# xmegs_breakout.net
KiCad netlist of a schematic drawn in EAGLE
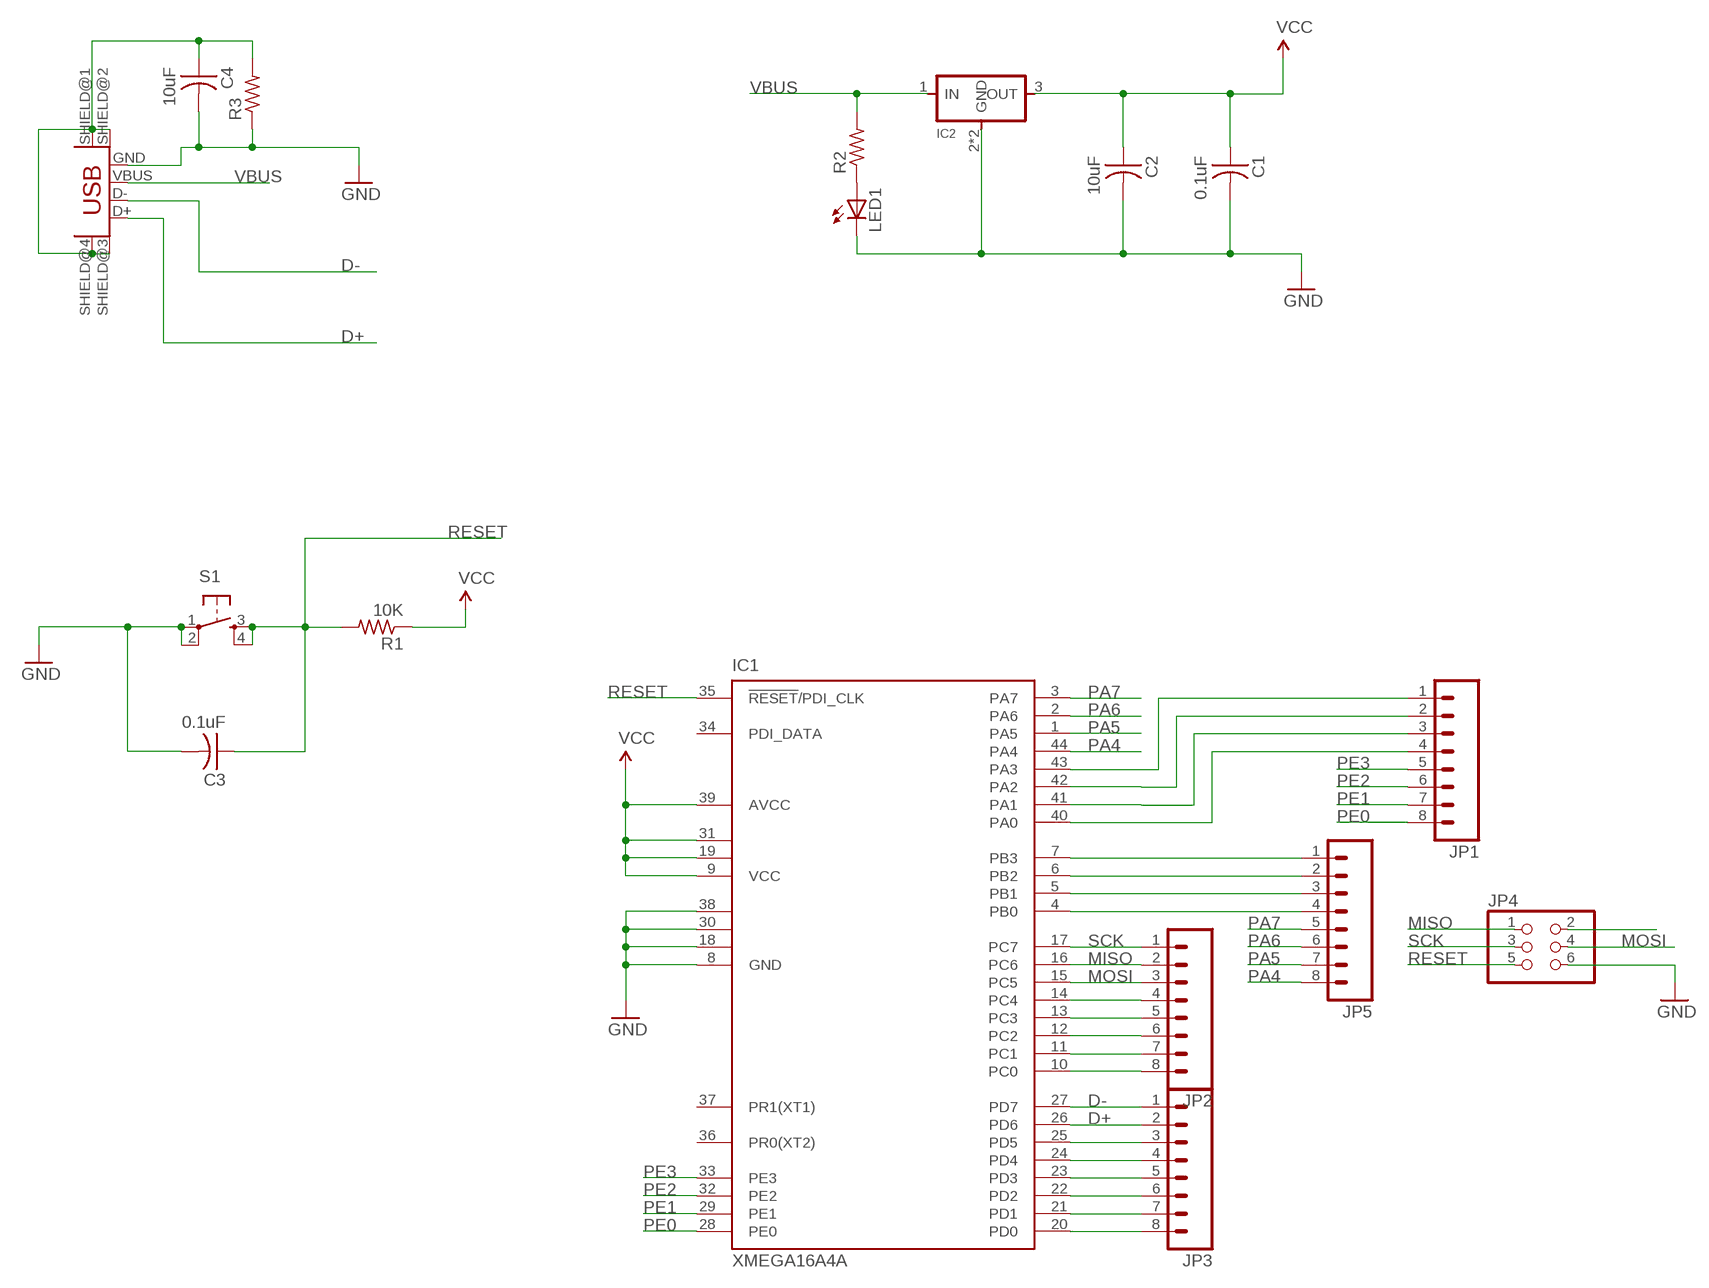
[diagram p0: schematic, sheet 1]

(export (version "E")
  (design (tool "Eeschema 10.0.6"))
  (components
    (comp (ref "C1")
      (value "0.1uF")
      (footprint "eagle-import:C1206")
      (libsource (lib "eagle-import") (part "CAP-US1206"))
    )
    (comp (ref "C2")
      (value "10uF")
      (footprint "eagle-import:C1206")
      (libsource (lib "eagle-import") (part "CAP-US1206"))
    )
    (comp (ref "C3")
      (value "0.1uF")
      (footprint "eagle-import:C1206")
      (libsource (lib "eagle-import") (part "CAP-US1206"))
    )
    (comp (ref "C4")
      (value "10uF")
      (footprint "eagle-import:C1206")
      (libsource (lib "eagle-import") (part "CAP-US1206"))
    )
    (comp (ref "IC1")
      (value "XMEGA16A4A")
      (footprint "eagle-import:TQFP44")
      (libsource (lib "eagle-import") (part "XMEGA16A4A"))
    )
    (comp (ref "IC2")
      (value "REGULATORSOT223")
      (footprint "eagle-import:SOT223")
      (libsource (lib "eagle-import") (part "REGULATORSOT223"))
    )
    (comp (ref "JP1")
      (value "M08")
      (footprint "eagle-import:1X08_SMD_ALT_2X1X4")
      (libsource (lib "eagle-import") (part "M08"))
    )
    (comp (ref "JP2")
      (value "M08SMD-STRAIGHT-ALT")
      (footprint "eagle-import:1X08_SMD_ALT")
      (libsource (lib "eagle-import") (part "M08SMD-STRAIGHT-ALT"))
    )
    (comp (ref "JP3")
      (value "M08SMD-STRAIGHT-ALT")
      (footprint "eagle-import:1X08_SMD_ALT")
      (libsource (lib "eagle-import") (part "M08SMD-STRAIGHT-ALT"))
    )
    (comp (ref "JP4")
      (value "PINHD-2X3-SMD")
      (footprint "eagle-import:2X03SMD")
      (libsource (lib "eagle-import") (part "PINHD-2X3-SMD"))
    )
    (comp (ref "JP5")
      (value "M08SMD-STRAIGHT-ALT")
      (footprint "eagle-import:1X08_SMD_ALT")
      (libsource (lib "eagle-import") (part "M08SMD-STRAIGHT-ALT"))
    )
    (comp (ref "LED1")
      (value "LEDSMT1206")
      (footprint "eagle-import:1206")
      (libsource (lib "eagle-import") (part "LEDSMT1206"))
    )
    (comp (ref "R1")
      (value "10K")
      (footprint "eagle-import:R1206FAB")
      (libsource (lib "eagle-import") (part "RES-US1206FAB"))
    )
    (comp (ref "R2")
      (value "RES-US1206FAB")
      (footprint "eagle-import:R1206FAB")
      (libsource (lib "eagle-import") (part "RES-US1206FAB"))
    )
    (comp (ref "R3")
      (value "RES-US1206FAB")
      (footprint "eagle-import:R1206FAB")
      (libsource (lib "eagle-import") (part "RES-US1206FAB"))
    )
    (comp (ref "S1")
      (value "6MM_SWITCH6MM_SWITCH")
      (footprint "eagle-import:6MM_SWITCH")
      (libsource (lib "eagle-import") (part "6MM_SWITCH6MM_SWITCH"))
    )
    (comp (ref "U$1")
      (value "USB_MINIB")
      (footprint "eagle-import:USB_MINIB")
      (libsource (lib "eagle-import") (part "USB_MINIB"))
    )
  )
  (nets
    (net (code "1") (name "/D+") (class "Default")
      (node (ref "IC1") (pin "26") (pinfunction "PD6_26") (pintype "bidirectional"))
      (node (ref "JP3") (pin "2") (pinfunction "2_2") (pintype "passive"))
      (node (ref "U$1") (pin "D+") (pinfunction "D+_D+") (pintype "bidirectional"))
    )
    (net (code "2") (name "/D-") (class "Default")
      (node (ref "IC1") (pin "27") (pinfunction "PD7_27") (pintype "bidirectional"))
      (node (ref "JP3") (pin "1") (pinfunction "1_1") (pintype "passive"))
      (node (ref "U$1") (pin "D-") (pinfunction "D-_D-") (pintype "bidirectional"))
    )
    (net (code "3") (name "/MISO") (class "Default")
      (node (ref "IC1") (pin "16") (pinfunction "PC6_16") (pintype "bidirectional"))
      (node (ref "JP2") (pin "2") (pinfunction "2_2") (pintype "passive"))
      (node (ref "JP4") (pin "1") (pinfunction "1_1") (pintype "passive"))
    )
    (net (code "4") (name "/MOSI") (class "Default")
      (node (ref "IC1") (pin "15") (pinfunction "PC5_15") (pintype "bidirectional"))
      (node (ref "JP2") (pin "3") (pinfunction "3_3") (pintype "passive"))
      (node (ref "JP4") (pin "4") (pinfunction "4_4") (pintype "passive"))
    )
    (net (code "5") (name "/PA4") (class "Default")
      (node (ref "IC1") (pin "44") (pinfunction "PA4_44") (pintype "bidirectional"))
      (node (ref "JP5") (pin "8") (pinfunction "8_8") (pintype "passive"))
    )
    (net (code "6") (name "/PA5") (class "Default")
      (node (ref "IC1") (pin "1") (pinfunction "PA5_1") (pintype "bidirectional"))
      (node (ref "JP5") (pin "7") (pinfunction "7_7") (pintype "passive"))
    )
    (net (code "7") (name "/PA6") (class "Default")
      (node (ref "IC1") (pin "2") (pinfunction "PA6_2") (pintype "bidirectional"))
      (node (ref "JP5") (pin "6") (pinfunction "6_6") (pintype "passive"))
    )
    (net (code "8") (name "/PA7") (class "Default")
      (node (ref "IC1") (pin "3") (pinfunction "PA7_3") (pintype "bidirectional"))
      (node (ref "JP5") (pin "5") (pinfunction "5_5") (pintype "passive"))
    )
    (net (code "9") (name "/PE0") (class "Default")
      (node (ref "IC1") (pin "28") (pinfunction "PE0_28") (pintype "bidirectional"))
      (node (ref "JP1") (pin "8") (pinfunction "8_8") (pintype "passive"))
    )
    (net (code "10") (name "/PE1") (class "Default")
      (node (ref "IC1") (pin "29") (pinfunction "PE1_29") (pintype "bidirectional"))
      (node (ref "JP1") (pin "7") (pinfunction "7_7") (pintype "passive"))
    )
    (net (code "11") (name "/PE2") (class "Default")
      (node (ref "IC1") (pin "32") (pinfunction "PE2_32") (pintype "bidirectional"))
      (node (ref "JP1") (pin "6") (pinfunction "6_6") (pintype "passive"))
    )
    (net (code "12") (name "/PE3") (class "Default")
      (node (ref "IC1") (pin "33") (pinfunction "PE3_33") (pintype "bidirectional"))
      (node (ref "JP1") (pin "5") (pinfunction "5_5") (pintype "passive"))
    )
    (net (code "13") (name "/RESET") (class "Default")
      (node (ref "C3") (pin "1") (pinfunction "1_1") (pintype "passive"))
      (node (ref "IC1") (pin "35") (pinfunction "~{RESET}/PDI_CLK_35") (pintype "bidirectional"))
      (node (ref "JP4") (pin "5") (pinfunction "5_5") (pintype "passive"))
      (node (ref "R1") (pin "2") (pinfunction "2_2") (pintype "passive"))
      (node (ref "S1") (pin "3") (pinfunction "S_3") (pintype "passive"))
      (node (ref "S1") (pin "4") (pinfunction "S1_4") (pintype "passive"))
    )
    (net (code "14") (name "/SCK") (class "Default")
      (node (ref "IC1") (pin "17") (pinfunction "PC7_17") (pintype "bidirectional"))
      (node (ref "JP2") (pin "1") (pinfunction "1_1") (pintype "passive"))
      (node (ref "JP4") (pin "3") (pinfunction "3_3") (pintype "passive"))
    )
    (net (code "15") (name "/VBUS") (class "Default")
      (node (ref "IC2") (pin "1") (pinfunction "IN_1") (pintype "bidirectional"))
      (node (ref "R2") (pin "2") (pinfunction "2_2") (pintype "passive"))
      (node (ref "U$1") (pin "VBUS") (pinfunction "VBUS_VBUS") (pintype "bidirectional"))
    )
    (net (code "16") (name "GND") (class "Default")
      (node (ref "C1") (pin "2") (pinfunction "2_2") (pintype "passive"))
      (node (ref "C2") (pin "2") (pinfunction "2_2") (pintype "passive"))
      (node (ref "C3") (pin "2") (pinfunction "2_2") (pintype "passive"))
      (node (ref "C4") (pin "2") (pinfunction "2_2") (pintype "passive"))
      (node (ref "IC1") (pin "18") (pinfunction "GND1_18") (pintype "power_in"))
      (node (ref "IC1") (pin "30") (pinfunction "GND2_30") (pintype "power_in"))
      (node (ref "IC1") (pin "38") (pinfunction "GND3_38") (pintype "power_in"))
      (node (ref "IC1") (pin "8") (pinfunction "GND_8") (pintype "power_in"))
      (node (ref "IC2") (pin "2") (pinfunction "GND_2") (pintype "bidirectional"))
      (node (ref "IC2") (pin "4") (pinfunction "GND_4") (pintype "bidirectional"))
      (node (ref "JP4") (pin "6") (pinfunction "6_6") (pintype "passive"))
      (node (ref "LED1") (pin "C") (pinfunction "C_C") (pintype "passive"))
      (node (ref "R3") (pin "1") (pinfunction "1_1") (pintype "passive"))
      (node (ref "S1") (pin "1") (pinfunction "P_1") (pintype "passive"))
      (node (ref "S1") (pin "2") (pinfunction "P1_2") (pintype "passive"))
      (node (ref "U$1") (pin "GND") (pinfunction "GND_GND") (pintype "bidirectional"))
    )
    (net (code "17") (name "Net-(IC1-PA0)") (class "Default")
      (node (ref "IC1") (pin "40") (pinfunction "PA0_40") (pintype "bidirectional"))
      (node (ref "JP1") (pin "4") (pinfunction "4_4") (pintype "passive"))
    )
    (net (code "18") (name "Net-(IC1-PA1)") (class "Default")
      (node (ref "IC1") (pin "41") (pinfunction "PA1_41") (pintype "bidirectional"))
      (node (ref "JP1") (pin "3") (pinfunction "3_3") (pintype "passive"))
    )
    (net (code "19") (name "Net-(IC1-PA2)") (class "Default")
      (node (ref "IC1") (pin "42") (pinfunction "PA2_42") (pintype "bidirectional"))
      (node (ref "JP1") (pin "2") (pinfunction "2_2") (pintype "passive"))
    )
    (net (code "20") (name "Net-(IC1-PA3)") (class "Default")
      (node (ref "IC1") (pin "43") (pinfunction "PA3_43") (pintype "bidirectional"))
      (node (ref "JP1") (pin "1") (pinfunction "1_1") (pintype "passive"))
    )
    (net (code "21") (name "Net-(IC1-PB0)") (class "Default")
      (node (ref "IC1") (pin "4") (pinfunction "PB0_4") (pintype "bidirectional"))
      (node (ref "JP5") (pin "4") (pinfunction "4_4") (pintype "passive"))
    )
    (net (code "22") (name "Net-(IC1-PB1)") (class "Default")
      (node (ref "IC1") (pin "5") (pinfunction "PB1_5") (pintype "bidirectional"))
      (node (ref "JP5") (pin "3") (pinfunction "3_3") (pintype "passive"))
    )
    (net (code "23") (name "Net-(IC1-PB2)") (class "Default")
      (node (ref "IC1") (pin "6") (pinfunction "PB2_6") (pintype "bidirectional"))
      (node (ref "JP5") (pin "2") (pinfunction "2_2") (pintype "passive"))
    )
    (net (code "24") (name "Net-(IC1-PB3)") (class "Default")
      (node (ref "IC1") (pin "7") (pinfunction "PB3_7") (pintype "bidirectional"))
      (node (ref "JP5") (pin "1") (pinfunction "1_1") (pintype "passive"))
    )
    (net (code "25") (name "Net-(IC1-PC0)") (class "Default")
      (node (ref "IC1") (pin "10") (pinfunction "PC0_10") (pintype "bidirectional"))
      (node (ref "JP2") (pin "8") (pinfunction "8_8") (pintype "passive"))
    )
    (net (code "26") (name "Net-(IC1-PC1)") (class "Default")
      (node (ref "IC1") (pin "11") (pinfunction "PC1_11") (pintype "bidirectional"))
      (node (ref "JP2") (pin "7") (pinfunction "7_7") (pintype "passive"))
    )
    (net (code "27") (name "Net-(IC1-PC2)") (class "Default")
      (node (ref "IC1") (pin "12") (pinfunction "PC2_12") (pintype "bidirectional"))
      (node (ref "JP2") (pin "6") (pinfunction "6_6") (pintype "passive"))
    )
    (net (code "28") (name "Net-(IC1-PC3)") (class "Default")
      (node (ref "IC1") (pin "13") (pinfunction "PC3_13") (pintype "bidirectional"))
      (node (ref "JP2") (pin "5") (pinfunction "5_5") (pintype "passive"))
    )
    (net (code "29") (name "Net-(IC1-PC4)") (class "Default")
      (node (ref "IC1") (pin "14") (pinfunction "PC4_14") (pintype "bidirectional"))
      (node (ref "JP2") (pin "4") (pinfunction "4_4") (pintype "passive"))
    )
    (net (code "30") (name "Net-(IC1-PD0)") (class "Default")
      (node (ref "IC1") (pin "20") (pinfunction "PD0_20") (pintype "bidirectional"))
      (node (ref "JP3") (pin "8") (pinfunction "8_8") (pintype "passive"))
    )
    (net (code "31") (name "Net-(IC1-PD1)") (class "Default")
      (node (ref "IC1") (pin "21") (pinfunction "PD1_21") (pintype "bidirectional"))
      (node (ref "JP3") (pin "7") (pinfunction "7_7") (pintype "passive"))
    )
    (net (code "32") (name "Net-(IC1-PD2)") (class "Default")
      (node (ref "IC1") (pin "22") (pinfunction "PD2_22") (pintype "bidirectional"))
      (node (ref "JP3") (pin "6") (pinfunction "6_6") (pintype "passive"))
    )
    (net (code "33") (name "Net-(IC1-PD3)") (class "Default")
      (node (ref "IC1") (pin "23") (pinfunction "PD3_23") (pintype "bidirectional"))
      (node (ref "JP3") (pin "5") (pinfunction "5_5") (pintype "passive"))
    )
    (net (code "34") (name "Net-(IC1-PD4)") (class "Default")
      (node (ref "IC1") (pin "24") (pinfunction "PD4_24") (pintype "bidirectional"))
      (node (ref "JP3") (pin "4") (pinfunction "4_4") (pintype "passive"))
    )
    (net (code "35") (name "Net-(IC1-PD5)") (class "Default")
      (node (ref "IC1") (pin "25") (pinfunction "PD5_25") (pintype "bidirectional"))
      (node (ref "JP3") (pin "3") (pinfunction "3_3") (pintype "passive"))
    )
    (net (code "36") (name "Net-(LED1-PadA)") (class "Default")
      (node (ref "LED1") (pin "A") (pinfunction "A_A") (pintype "passive"))
      (node (ref "R2") (pin "1") (pinfunction "1_1") (pintype "passive"))
    )
    (net (code "37") (name "Net-(U$1-SHIELD)") (class "Default")
      (node (ref "C4") (pin "1") (pinfunction "1_1") (pintype "passive"))
      (node (ref "R3") (pin "2") (pinfunction "2_2") (pintype "passive"))
      (node (ref "U$1") (pin "SHIELD@1") (pinfunction "SHIELD_SHIELD@1") (pintype "passive"))
      (node (ref "U$1") (pin "SHIELD@2") (pinfunction "SHIELD1_SHIELD@2") (pintype "passive"))
      (node (ref "U$1") (pin "SHIELD@3") (pinfunction "SHIELD2_SHIELD@3") (pintype "passive"))
      (node (ref "U$1") (pin "SHIELD@4") (pinfunction "SHIELD3_SHIELD@4") (pintype "passive"))
    )
    (net (code "38") (name "VCC") (class "Default")
      (node (ref "C1") (pin "1") (pinfunction "1_1") (pintype "passive"))
      (node (ref "C2") (pin "1") (pinfunction "1_1") (pintype "passive"))
      (node (ref "IC1") (pin "19") (pinfunction "VCC1_19") (pintype "power_in"))
      (node (ref "IC1") (pin "31") (pinfunction "VCC2_31") (pintype "power_in"))
      (node (ref "IC1") (pin "39") (pinfunction "AVCC_39") (pintype "power_in"))
      (node (ref "IC1") (pin "9") (pinfunction "VCC_9") (pintype "power_in"))
      (node (ref "IC2") (pin "3") (pinfunction "OUT_3") (pintype "bidirectional"))
      (node (ref "R1") (pin "1") (pinfunction "1_1") (pintype "passive"))
    )
    (net (code "39") (name "unconnected-(IC1-PDI_DATA-Pad34)") (class "Default")
      (node (ref "IC1") (pin "34") (pinfunction "PDI_DATA_34") (pintype "bidirectional"))
    )
    (net (code "40") (name "unconnected-(IC1-PR0(XT2)-Pad36)") (class "Default")
      (node (ref "IC1") (pin "36") (pinfunction "PR0(XT2)_36") (pintype "bidirectional"))
    )
    (net (code "41") (name "unconnected-(IC1-PR1(XT1)-Pad37)") (class "Default")
      (node (ref "IC1") (pin "37") (pinfunction "PR1(XT1)_37") (pintype "bidirectional"))
    )
    (net (code "42") (name "unconnected-(JP4-Pad2)") (class "Default")
      (node (ref "JP4") (pin "2") (pinfunction "2_2") (pintype "passive"))
    )
  )
)
